# bcard.net
KiCad netlist of a schematic drawn in EAGLE
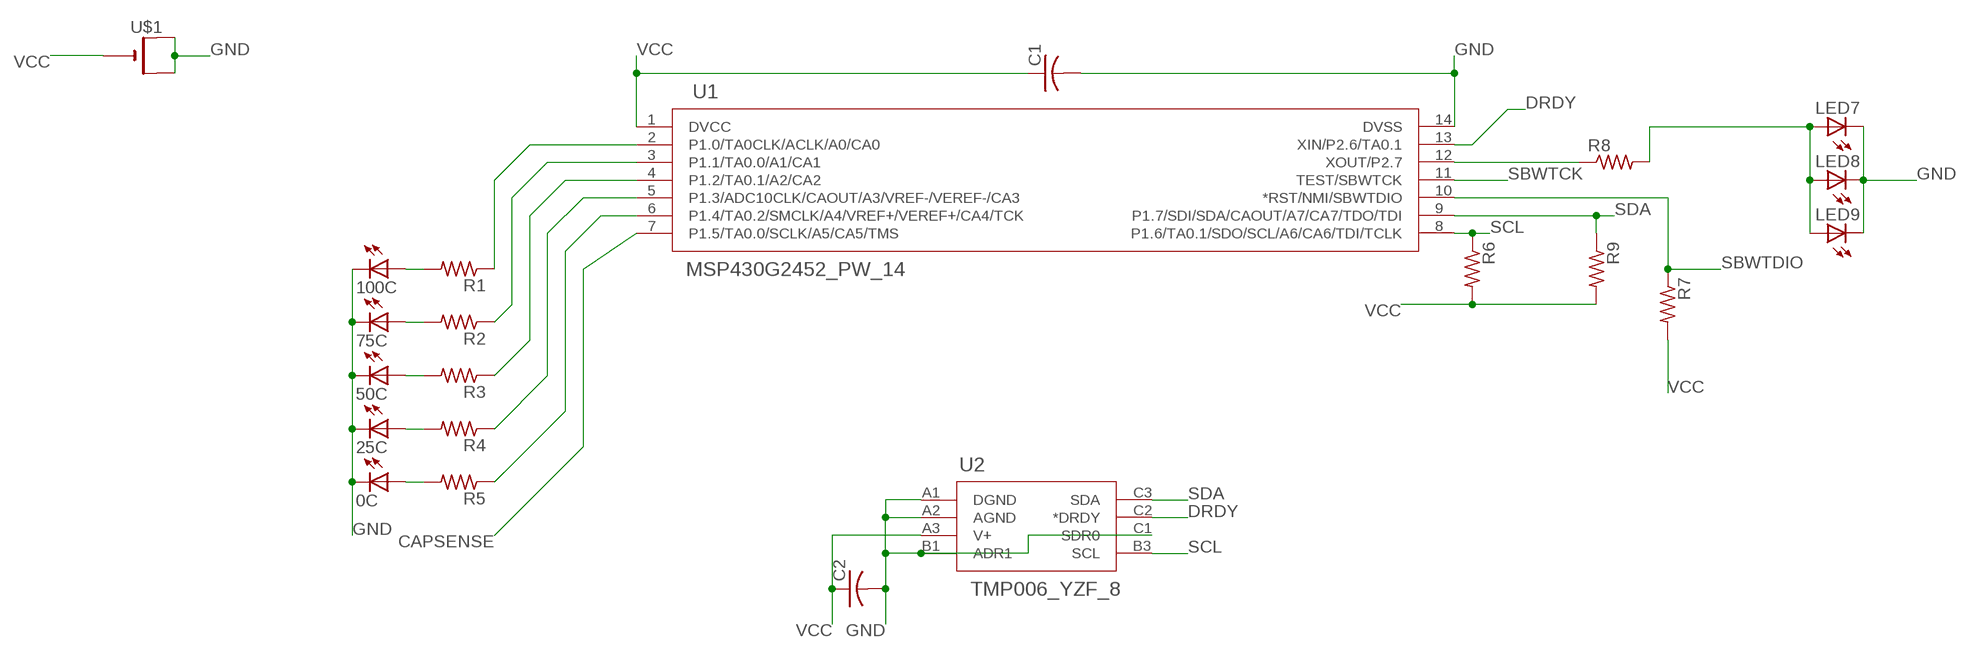
[diagram p0: schematic, sheet 1]

(export (version "E")
  (design (tool "Eeschema 10.0.6"))
  (components
    (comp (ref "0C")
      (value "LEDCHIP-LED0805")
      (footprint "eagle-import:CHIP-LED0805")
      (libsource (lib "eagle-import") (part "LEDCHIP-LED0805"))
    )
    (comp (ref "25C")
      (value "LEDCHIP-LED0805")
      (footprint "eagle-import:CHIP-LED0805")
      (libsource (lib "eagle-import") (part "LEDCHIP-LED0805"))
    )
    (comp (ref "50C")
      (value "LEDCHIP-LED0805")
      (footprint "eagle-import:CHIP-LED0805")
      (libsource (lib "eagle-import") (part "LEDCHIP-LED0805"))
    )
    (comp (ref "75C")
      (value "LEDCHIP-LED0805")
      (footprint "eagle-import:CHIP-LED0805")
      (libsource (lib "eagle-import") (part "LEDCHIP-LED0805"))
    )
    (comp (ref "100C")
      (value "LEDCHIP-LED0805")
      (footprint "eagle-import:CHIP-LED0805")
      (libsource (lib "eagle-import") (part "LEDCHIP-LED0805"))
    )
    (comp (ref "C1")
      (value "C-USC0805")
      (footprint "eagle-import:C0805")
      (libsource (lib "eagle-import") (part "C-USC0805"))
    )
    (comp (ref "C2")
      (value "C-USC0805")
      (footprint "eagle-import:C0805")
      (libsource (lib "eagle-import") (part "C-USC0805"))
    )
    (comp (ref "LED7")
      (value "LEDCHIP-LED0805")
      (footprint "eagle-import:CHIP-LED0805")
      (libsource (lib "eagle-import") (part "LEDCHIP-LED0805"))
    )
    (comp (ref "LED8")
      (value "LEDCHIP-LED0805")
      (footprint "eagle-import:CHIP-LED0805")
      (libsource (lib "eagle-import") (part "LEDCHIP-LED0805"))
    )
    (comp (ref "LED9")
      (value "LEDCHIP-LED0805")
      (footprint "eagle-import:CHIP-LED0805")
      (libsource (lib "eagle-import") (part "LEDCHIP-LED0805"))
    )
    (comp (ref "R1")
      (value "R-US_R0805")
      (footprint "eagle-import:R0805")
      (libsource (lib "eagle-import") (part "R-US_R0805"))
    )
    (comp (ref "R2")
      (value "R-US_R0805")
      (footprint "eagle-import:R0805")
      (libsource (lib "eagle-import") (part "R-US_R0805"))
    )
    (comp (ref "R3")
      (value "R-US_R0805")
      (footprint "eagle-import:R0805")
      (libsource (lib "eagle-import") (part "R-US_R0805"))
    )
    (comp (ref "R4")
      (value "R-US_R0805")
      (footprint "eagle-import:R0805")
      (libsource (lib "eagle-import") (part "R-US_R0805"))
    )
    (comp (ref "R5")
      (value "R-US_R0805")
      (footprint "eagle-import:R0805")
      (libsource (lib "eagle-import") (part "R-US_R0805"))
    )
    (comp (ref "R6")
      (value "R-US_R0805")
      (footprint "eagle-import:R0805")
      (libsource (lib "eagle-import") (part "R-US_R0805"))
    )
    (comp (ref "R7")
      (value "R-US_R0805")
      (footprint "eagle-import:R0805")
      (libsource (lib "eagle-import") (part "R-US_R0805"))
    )
    (comp (ref "R8")
      (value "R-US_R0805")
      (footprint "eagle-import:R0805")
      (libsource (lib "eagle-import") (part "R-US_R0805"))
    )
    (comp (ref "R9")
      (value "R-US_R0805")
      (footprint "eagle-import:R0805")
      (libsource (lib "eagle-import") (part "R-US_R0805"))
    )
    (comp (ref "U$1")
      (value "CR1220SMT")
      (footprint "eagle-import:CR1220-SMD")
      (libsource (lib "eagle-import") (part "CR1220SMT"))
    )
    (comp (ref "U1")
      (value "MSP430G2452_PW_14")
      (footprint "eagle-import:PW14")
      (fields
        (field (name "GENERIC_PART_NUMBER") "MSP430G2452")
        (field (name "MANUFACTURER") "Texas Instruments")
        (field (name "MANUFACTURER_PART_NUMBER") "msp430g2452_pw_14")
      )
      (libsource (lib "eagle-import") (part "MSP430G2452_PW_14"))
    )
    (comp (ref "U2")
      (value "TMP006_YZF_8")
      (footprint "eagle-import:YZF8")
      (fields
        (field (name "GENERIC_PART_NUMBER") "TMP006")
        (field (name "MANUFACTURER") "Texas Instruments")
        (field (name "MANUFACTURER_PART_NUMBER") "tmp006_yzf_8")
      )
      (libsource (lib "eagle-import") (part "TMP006_YZF_8"))
    )
  )
  (nets
    (net (code "1") (name "/CAPSENSE") (class "Default")
      (node (ref "U1") (pin "7") (pinfunction "P1.5/TA0.0/SCLK/A5/CA5/TMS_7") (pintype "bidirectional"))
    )
    (net (code "2") (name "/DRDY") (class "Default")
      (node (ref "U1") (pin "13") (pinfunction "XIN/P2.6/TA0.1_13") (pintype "bidirectional"))
      (node (ref "U2") (pin "C2") (pinfunction "*DRDY_C2") (pintype "passive"))
    )
    (net (code "3") (name "/GND") (class "Default")
      (node (ref "0C") (pin "C") (pinfunction "C_C") (pintype "passive"))
      (node (ref "100C") (pin "C") (pinfunction "C_C") (pintype "passive"))
      (node (ref "25C") (pin "C") (pinfunction "C_C") (pintype "passive"))
      (node (ref "50C") (pin "C") (pinfunction "C_C") (pintype "passive"))
      (node (ref "75C") (pin "C") (pinfunction "C_C") (pintype "passive"))
      (node (ref "C1") (pin "2") (pinfunction "2_2") (pintype "passive"))
      (node (ref "C2") (pin "2") (pinfunction "2_2") (pintype "passive"))
      (node (ref "LED7") (pin "C") (pinfunction "C_C") (pintype "passive"))
      (node (ref "LED8") (pin "C") (pinfunction "C_C") (pintype "passive"))
      (node (ref "LED9") (pin "C") (pinfunction "C_C") (pintype "passive"))
      (node (ref "U$1") (pin "+$1") (pinfunction "+_+$1") (pintype "passive"))
      (node (ref "U$1") (pin "+$2") (pinfunction "+1_+$2") (pintype "passive"))
      (node (ref "U1") (pin "14") (pinfunction "DVSS_14") (pintype "power_in"))
      (node (ref "U2") (pin "A1") (pinfunction "DGND_A1") (pintype "power_in"))
      (node (ref "U2") (pin "A2") (pinfunction "AGND_A2") (pintype "power_in"))
      (node (ref "U2") (pin "B1") (pinfunction "ADR1_B1") (pintype "passive"))
      (node (ref "U2") (pin "C1") (pinfunction "SDR0_C1") (pintype "passive"))
    )
    (net (code "4") (name "/SBWTCK") (class "Default")
      (node (ref "U1") (pin "11") (pinfunction "TEST/SBWTCK_11") (pintype "bidirectional"))
    )
    (net (code "5") (name "/SBWTDIO") (class "Default")
      (node (ref "R7") (pin "1") (pinfunction "1_1") (pintype "passive"))
      (node (ref "U1") (pin "10") (pinfunction "*RST/NMI/SBWTDIO_10") (pintype "bidirectional"))
    )
    (net (code "6") (name "/SCL") (class "Default")
      (node (ref "R6") (pin "1") (pinfunction "1_1") (pintype "passive"))
      (node (ref "U1") (pin "8") (pinfunction "P1.6/TA0.1/SDO/SCL/A6/CA6/TDI/TCLK_8") (pintype "bidirectional"))
      (node (ref "U2") (pin "B3") (pinfunction "SCL_B3") (pintype "passive"))
    )
    (net (code "7") (name "/SDA") (class "Default")
      (node (ref "R9") (pin "1") (pinfunction "1_1") (pintype "passive"))
      (node (ref "U1") (pin "9") (pinfunction "P1.7/SDI/SDA/CAOUT/A7/CA7/TDO/TDI_9") (pintype "bidirectional"))
      (node (ref "U2") (pin "C3") (pinfunction "SDA_C3") (pintype "passive"))
    )
    (net (code "8") (name "/VCC") (class "Default")
      (node (ref "C1") (pin "1") (pinfunction "1_1") (pintype "passive"))
      (node (ref "C2") (pin "1") (pinfunction "1_1") (pintype "passive"))
      (node (ref "R6") (pin "2") (pinfunction "2_2") (pintype "passive"))
      (node (ref "R7") (pin "2") (pinfunction "2_2") (pintype "passive"))
      (node (ref "R9") (pin "2") (pinfunction "2_2") (pintype "passive"))
      (node (ref "U$1") (pin "-") (pinfunction "-_-") (pintype "passive"))
      (node (ref "U1") (pin "1") (pinfunction "DVCC_1") (pintype "power_in"))
      (node (ref "U2") (pin "A3") (pinfunction "V+_A3") (pintype "power_in"))
    )
    (net (code "9") (name "Net-(0C-PadA)") (class "Default")
      (node (ref "0C") (pin "A") (pinfunction "A_A") (pintype "passive"))
      (node (ref "R5") (pin "2") (pinfunction "2_2") (pintype "passive"))
    )
    (net (code "10") (name "Net-(25C-PadA)") (class "Default")
      (node (ref "25C") (pin "A") (pinfunction "A_A") (pintype "passive"))
      (node (ref "R4") (pin "2") (pinfunction "2_2") (pintype "passive"))
    )
    (net (code "11") (name "Net-(50C-PadA)") (class "Default")
      (node (ref "50C") (pin "A") (pinfunction "A_A") (pintype "passive"))
      (node (ref "R3") (pin "2") (pinfunction "2_2") (pintype "passive"))
    )
    (net (code "12") (name "Net-(75C-PadA)") (class "Default")
      (node (ref "75C") (pin "A") (pinfunction "A_A") (pintype "passive"))
      (node (ref "R2") (pin "2") (pinfunction "2_2") (pintype "passive"))
    )
    (net (code "13") (name "Net-(100C-PadA)") (class "Default")
      (node (ref "100C") (pin "A") (pinfunction "A_A") (pintype "passive"))
      (node (ref "R1") (pin "2") (pinfunction "2_2") (pintype "passive"))
    )
    (net (code "14") (name "Net-(LED7-PadA)") (class "Default")
      (node (ref "LED7") (pin "A") (pinfunction "A_A") (pintype "passive"))
      (node (ref "LED8") (pin "A") (pinfunction "A_A") (pintype "passive"))
      (node (ref "LED9") (pin "A") (pinfunction "A_A") (pintype "passive"))
      (node (ref "R8") (pin "2") (pinfunction "2_2") (pintype "passive"))
    )
    (net (code "15") (name "Net-(U1-P1.0{slash}TA0CLK{slash}ACLK{slash}A0{slash}CA0)") (class "Default")
      (node (ref "R1") (pin "1") (pinfunction "1_1") (pintype "passive"))
      (node (ref "U1") (pin "2") (pinfunction "P1.0/TA0CLK/ACLK/A0/CA0_2") (pintype "bidirectional"))
    )
    (net (code "16") (name "Net-(U1-P1.1{slash}TA0.0{slash}A1{slash}CA1)") (class "Default")
      (node (ref "R2") (pin "1") (pinfunction "1_1") (pintype "passive"))
      (node (ref "U1") (pin "3") (pinfunction "P1.1/TA0.0/A1/CA1_3") (pintype "bidirectional"))
    )
    (net (code "17") (name "Net-(U1-P1.2{slash}TA0.1{slash}A2{slash}CA2)") (class "Default")
      (node (ref "R3") (pin "1") (pinfunction "1_1") (pintype "passive"))
      (node (ref "U1") (pin "4") (pinfunction "P1.2/TA0.1/A2/CA2_4") (pintype "bidirectional"))
    )
    (net (code "18") (name "Net-(U1-P1.3{slash}ADC10CLK{slash}CAOUT{slash}A3{slash}VREF-{slash}VEREF-{slash}CA3)") (class "Default")
      (node (ref "R4") (pin "1") (pinfunction "1_1") (pintype "passive"))
      (node (ref "U1") (pin "5") (pinfunction "P1.3/ADC10CLK/CAOUT/A3/VREF-/VEREF-/CA3_5") (pintype "bidirectional"))
    )
    (net (code "19") (name "Net-(U1-P1.4{slash}TA0.2{slash}SMCLK{slash}A4{slash}VREF+{slash}VEREF+{slash}CA4{slash}TCK)") (class "Default")
      (node (ref "R5") (pin "1") (pinfunction "1_1") (pintype "passive"))
      (node (ref "U1") (pin "6") (pinfunction "P1.4/TA0.2/SMCLK/A4/VREF+/VEREF+/CA4/TCK_6") (pintype "bidirectional"))
    )
    (net (code "20") (name "Net-(U1-XOUT{slash}P2.7)") (class "Default")
      (node (ref "R8") (pin "1") (pinfunction "1_1") (pintype "passive"))
      (node (ref "U1") (pin "12") (pinfunction "XOUT/P2.7_12") (pintype "bidirectional"))
    )
  )
)
